# generator4.net
KiCad netlist of a schematic drawn in EAGLE
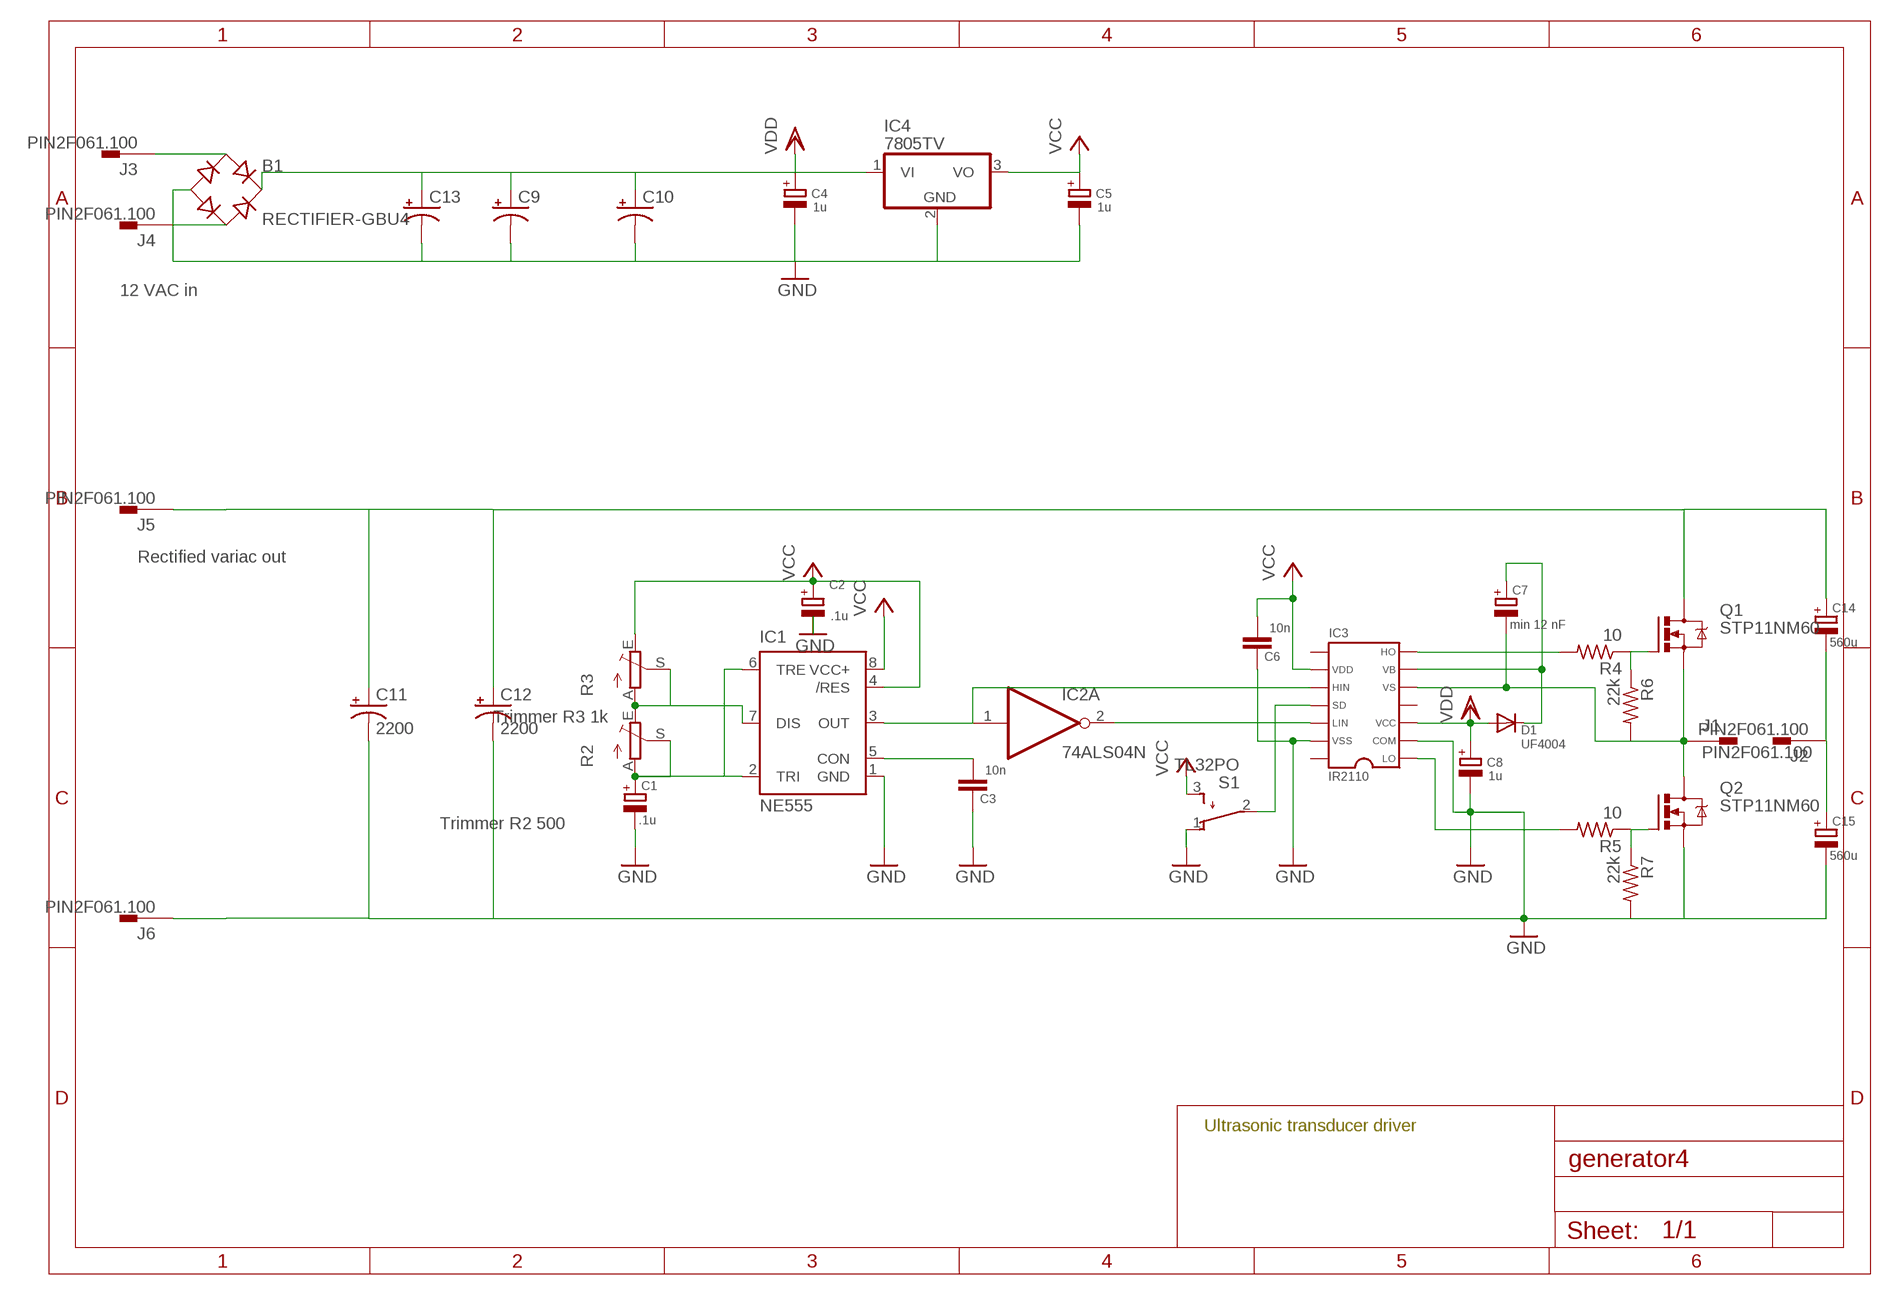
[diagram p0: schematic, sheet 1]

(export (version "E")
  (design (tool "Eeschema 10.0.6"))
  (components
    (comp (ref "B1")
      (value "RECTIFIER-GBU4")
      (footprint "eagle-import:GBU4")
      (libsource (lib "eagle-import") (part "RECTIFIER-GBU4"))
    )
    (comp (ref "C1")
      (value ".1u")
      (footprint "eagle-import:E5-8,5")
      (libsource (lib "eagle-import") (part "CPOL-EUE5-8.5"))
    )
    (comp (ref "C2")
      (value ".1u")
      (footprint "eagle-import:E5-8,5")
      (libsource (lib "eagle-import") (part "CPOL-EUE5-8.5"))
    )
    (comp (ref "C3")
      (value "10n")
      (footprint "eagle-import:C075-052X106")
      (libsource (lib "eagle-import") (part "C-EU075-052X106"))
    )
    (comp (ref "C4")
      (value "1u")
      (footprint "eagle-import:E5-8,5")
      (libsource (lib "eagle-import") (part "CPOL-EUE5-8.5"))
    )
    (comp (ref "C5")
      (value "1u")
      (footprint "eagle-import:E5-8,5")
      (libsource (lib "eagle-import") (part "CPOL-EUE5-8.5"))
    )
    (comp (ref "C6")
      (value "10n")
      (footprint "eagle-import:C075-052X106")
      (libsource (lib "eagle-import") (part "C-EU075-052X106"))
    )
    (comp (ref "C7")
      (value "min 12 nF")
      (footprint "eagle-import:E5-8,5")
      (libsource (lib "eagle-import") (part "CPOL-EUE5-8.5"))
    )
    (comp (ref "C8")
      (value "1u")
      (footprint "eagle-import:E5-8,5")
      (libsource (lib "eagle-import") (part "CPOL-EUE5-8.5"))
    )
    (comp (ref "C9")
      (value "CPOL-USE7.5-18")
      (footprint "eagle-import:E7,5-18")
      (libsource (lib "eagle-import") (part "CPOL-USE7.5-18"))
    )
    (comp (ref "C10")
      (value "CPOL-USE7.5-18")
      (footprint "eagle-import:E7,5-18")
      (libsource (lib "eagle-import") (part "CPOL-USE7.5-18"))
    )
    (comp (ref "C11")
      (value "2200")
      (footprint "eagle-import:EB35D")
      (libsource (lib "eagle-import") (part "CPOL-USE10-35"))
    )
    (comp (ref "C12")
      (value "2200")
      (footprint "eagle-import:EB35D")
      (libsource (lib "eagle-import") (part "CPOL-USE10-35"))
    )
    (comp (ref "C13")
      (value "CPOL-USE7.5-18")
      (footprint "eagle-import:E7,5-18")
      (libsource (lib "eagle-import") (part "CPOL-USE7.5-18"))
    )
    (comp (ref "C14")
      (value "560u")
      (footprint "eagle-import:E7,5-16")
      (libsource (lib "eagle-import") (part "CPOL-EUE7.5-16"))
    )
    (comp (ref "C15")
      (value "560u")
      (footprint "eagle-import:E7,5-16")
      (libsource (lib "eagle-import") (part "CPOL-EUE7.5-16"))
    )
    (comp (ref "D1")
      (value "UF4004")
      (footprint "eagle-import:D-7.5")
      (libsource (lib "eagle-import") (part "DIODE-D-7.5"))
    )
    (comp (ref "IC1")
      (value "NE555")
      (footprint "eagle-import:DIL-08")
      (fields (field (name "MF") "Arrow Electronics") (field (name "MPN") "NE555N"))
      (libsource (lib "eagle-import") (part "NE555"))
    )
    (comp (ref "IC2")
      (value "74ALS04N")
      (footprint "eagle-import:DIL14")
      (libsource (lib "eagle-import") (part "7404NALS"))
    )
    (comp (ref "IC3")
      (value "IR2110")
      (footprint "eagle-import:DIL14")
      (libsource (lib "eagle-import") (part "IR2110"))
    )
    (comp (ref "IC4")
      (value "7805TV")
      (footprint "eagle-import:TO220V")
      (libsource (lib "eagle-import") (part "78TV05"))
    )
    (comp (ref "J1")
      (value "PIN2F061.100")
      (footprint "eagle-import:F061.100")
      (libsource (lib "eagle-import") (part "PIN2F061.100"))
    )
    (comp (ref "J2")
      (value "PIN2F061.100")
      (footprint "eagle-import:F061.100")
      (libsource (lib "eagle-import") (part "PIN2F061.100"))
    )
    (comp (ref "J3")
      (value "PIN2F061.100")
      (footprint "eagle-import:F061.100")
      (libsource (lib "eagle-import") (part "PIN2F061.100"))
    )
    (comp (ref "J4")
      (value "PIN2F061.100")
      (footprint "eagle-import:F061.100")
      (libsource (lib "eagle-import") (part "PIN2F061.100"))
    )
    (comp (ref "J5")
      (value "PIN2F061.100")
      (footprint "eagle-import:F061.100")
      (libsource (lib "eagle-import") (part "PIN2F061.100"))
    )
    (comp (ref "J6")
      (value "PIN2F061.100")
      (footprint "eagle-import:F061.100")
      (libsource (lib "eagle-import") (part "PIN2F061.100"))
    )
    (comp (ref "Q1")
      (value "STP11NM60")
      (footprint "eagle-import:TO220BV")
      (libsource (lib "eagle-import") (part "IRF530"))
    )
    (comp (ref "Q2")
      (value "STP11NM60")
      (footprint "eagle-import:TO220BV")
      (libsource (lib "eagle-import") (part "IRF530"))
    )
    (comp (ref "R2")
      (value "TRIM_EU-LI10")
      (footprint "eagle-import:LI10")
      (libsource (lib "eagle-import") (part "TRIM_EU-LI10"))
    )
    (comp (ref "R3")
      (value "TRIM_EU-LI10")
      (footprint "eagle-import:LI10")
      (libsource (lib "eagle-import") (part "TRIM_EU-LI10"))
    )
    (comp (ref "R4")
      (value "10")
      (footprint "eagle-import:0207_10")
      (libsource (lib "eagle-import") (part "R-US_0207/10"))
    )
    (comp (ref "R5")
      (value "10")
      (footprint "eagle-import:0207_10")
      (libsource (lib "eagle-import") (part "R-US_0207/10"))
    )
    (comp (ref "R6")
      (value "22k")
      (footprint "eagle-import:0207_10")
      (libsource (lib "eagle-import") (part "R-US_0207/10"))
    )
    (comp (ref "R7")
      (value "22k")
      (footprint "eagle-import:0207_10")
      (libsource (lib "eagle-import") (part "R-US_0207/10"))
    )
    (comp (ref "S1")
      (value "TL32PO")
      (footprint "eagle-import:TL3XPO")
      (libsource (lib "eagle-import") (part "TL32PO"))
    )
  )
  (nets
    (net (code "1") (name "GND") (class "Default")
      (node (ref "B1") (pin "-") (pinfunction "-_-") (pintype "passive"))
      (node (ref "C1") (pin "-") (pinfunction "-_-") (pintype "passive"))
      (node (ref "C10") (pin "-") (pinfunction "-_-") (pintype "passive"))
      (node (ref "C11") (pin "-") (pinfunction "-_-") (pintype "passive"))
      (node (ref "C12") (pin "-") (pinfunction "-_-") (pintype "passive"))
      (node (ref "C13") (pin "-") (pinfunction "-_-") (pintype "passive"))
      (node (ref "C15") (pin "-") (pinfunction "-_-") (pintype "passive"))
      (node (ref "C2") (pin "-") (pinfunction "-_-") (pintype "passive"))
      (node (ref "C3") (pin "1") (pinfunction "1_1") (pintype "passive"))
      (node (ref "C4") (pin "-") (pinfunction "-_-") (pintype "passive"))
      (node (ref "C5") (pin "-") (pinfunction "-_-") (pintype "passive"))
      (node (ref "C6") (pin "1") (pinfunction "1_1") (pintype "passive"))
      (node (ref "C8") (pin "-") (pinfunction "-_-") (pintype "passive"))
      (node (ref "C9") (pin "-") (pinfunction "-_-") (pintype "passive"))
      (node (ref "IC1") (pin "1") (pinfunction "GND_1") (pintype "power_in"))
      (node (ref "IC3") (pin "13") (pinfunction "13_13") (pintype "passive"))
      (node (ref "IC3") (pin "2") (pinfunction "2_2") (pintype "passive"))
      (node (ref "IC4") (pin "2") (pinfunction "GND_2") (pintype "passive"))
      (node (ref "J6") (pin "A1") (pinfunction "1_A1") (pintype "passive"))
      (node (ref "J6") (pin "A2") (pinfunction "1_A2") (pintype "passive"))
      (node (ref "Q2") (pin "S") (pinfunction "S_S") (pintype "passive"))
      (node (ref "R7") (pin "2") (pinfunction "2_2") (pintype "passive"))
      (node (ref "S1") (pin "1") (pinfunction "O_1") (pintype "passive"))
    )
    (net (code "2") (name "Net-(B1-PadAC1)") (class "Default")
      (node (ref "B1") (pin "AC1") (pinfunction "AC1_AC1") (pintype "passive"))
      (node (ref "J3") (pin "A1") (pinfunction "1_A1") (pintype "passive"))
      (node (ref "J3") (pin "A2") (pinfunction "1_A2") (pintype "passive"))
    )
    (net (code "3") (name "Net-(B1-PadAC2)") (class "Default")
      (node (ref "B1") (pin "AC2") (pinfunction "AC2_AC2") (pintype "passive"))
      (node (ref "J4") (pin "A1") (pinfunction "1_A1") (pintype "passive"))
      (node (ref "J4") (pin "A2") (pinfunction "1_A2") (pintype "passive"))
    )
    (net (code "4") (name "Net-(C7-Pad+)") (class "Default")
      (node (ref "C7") (pin "+") (pinfunction "+_+") (pintype "passive"))
      (node (ref "D1") (pin "C") (pinfunction "C_C") (pintype "passive"))
      (node (ref "IC3") (pin "6") (pinfunction "6_6") (pintype "passive"))
    )
    (net (code "5") (name "Net-(C7-Pad-)") (class "Default")
      (node (ref "C7") (pin "-") (pinfunction "-_-") (pintype "passive"))
      (node (ref "IC3") (pin "5") (pinfunction "5_5") (pintype "passive"))
      (node (ref "J1") (pin "A1") (pinfunction "1_A1") (pintype "passive"))
      (node (ref "J1") (pin "A2") (pinfunction "1_A2") (pintype "passive"))
      (node (ref "Q1") (pin "S") (pinfunction "S_S") (pintype "passive"))
      (node (ref "Q2") (pin "D") (pinfunction "D_D") (pintype "passive"))
      (node (ref "R6") (pin "2") (pinfunction "2_2") (pintype "passive"))
    )
    (net (code "6") (name "Net-(C11-Pad+)") (class "Default")
      (node (ref "C11") (pin "+") (pinfunction "+_+") (pintype "passive"))
      (node (ref "C12") (pin "+") (pinfunction "+_+") (pintype "passive"))
      (node (ref "C14") (pin "+") (pinfunction "+_+") (pintype "passive"))
      (node (ref "J5") (pin "A1") (pinfunction "1_A1") (pintype "passive"))
      (node (ref "J5") (pin "A2") (pinfunction "1_A2") (pintype "passive"))
      (node (ref "Q1") (pin "D") (pinfunction "D_D") (pintype "passive"))
    )
    (net (code "7") (name "Net-(C14-Pad-)") (class "Default")
      (node (ref "C14") (pin "-") (pinfunction "-_-") (pintype "passive"))
      (node (ref "C15") (pin "+") (pinfunction "+_+") (pintype "passive"))
      (node (ref "J2") (pin "A1") (pinfunction "1_A1") (pintype "passive"))
      (node (ref "J2") (pin "A2") (pinfunction "1_A2") (pintype "passive"))
    )
    (net (code "8") (name "Net-(IC1-CON)") (class "Default")
      (node (ref "C3") (pin "2") (pinfunction "2_2") (pintype "passive"))
      (node (ref "IC1") (pin "5") (pinfunction "CON_5") (pintype "input"))
    )
    (net (code "9") (name "Net-(IC1-DIS)") (class "Default")
      (node (ref "IC1") (pin "7") (pinfunction "DIS_7") (pintype "input"))
      (node (ref "R2") (pin "E") (pinfunction "E_E") (pintype "passive"))
      (node (ref "R3") (pin "A") (pinfunction "A_A") (pintype "passive"))
      (node (ref "R3") (pin "S") (pinfunction "S_S") (pintype "passive"))
    )
    (net (code "10") (name "Net-(IC1-OUT)") (class "Default")
      (node (ref "IC1") (pin "3") (pinfunction "OUT_3") (pintype "output"))
      (node (ref "IC2") (pin "1") (pinfunction "I_1") (pintype "input"))
      (node (ref "IC3") (pin "10") (pinfunction "10_10") (pintype "passive"))
    )
    (net (code "11") (name "Net-(IC1-TRE)") (class "Default")
      (node (ref "C1") (pin "+") (pinfunction "+_+") (pintype "passive"))
      (node (ref "IC1") (pin "2") (pinfunction "TRI_2") (pintype "input"))
      (node (ref "IC1") (pin "6") (pinfunction "TRE_6") (pintype "input"))
      (node (ref "R2") (pin "A") (pinfunction "A_A") (pintype "passive"))
      (node (ref "R2") (pin "S") (pinfunction "S_S") (pintype "passive"))
    )
    (net (code "12") (name "Net-(IC2A-O)") (class "Default")
      (node (ref "IC2") (pin "2") (pinfunction "O_2") (pintype "output"))
      (node (ref "IC3") (pin "12") (pinfunction "12_12") (pintype "passive"))
    )
    (net (code "13") (name "Net-(IC3-Pad1)") (class "Default")
      (node (ref "IC3") (pin "1") (pinfunction "1_1") (pintype "passive"))
      (node (ref "R5") (pin "2") (pinfunction "2_2") (pintype "passive"))
    )
    (net (code "14") (name "Net-(IC3-Pad7)") (class "Default")
      (node (ref "IC3") (pin "7") (pinfunction "7_7") (pintype "passive"))
      (node (ref "R4") (pin "2") (pinfunction "2_2") (pintype "passive"))
    )
    (net (code "15") (name "Net-(Q1-PadG)") (class "Default")
      (node (ref "Q1") (pin "G") (pinfunction "G_G") (pintype "passive"))
      (node (ref "R4") (pin "1") (pinfunction "1_1") (pintype "passive"))
      (node (ref "R6") (pin "1") (pinfunction "1_1") (pintype "passive"))
    )
    (net (code "16") (name "Net-(Q2-PadG)") (class "Default")
      (node (ref "Q2") (pin "G") (pinfunction "G_G") (pintype "passive"))
      (node (ref "R5") (pin "1") (pinfunction "1_1") (pintype "passive"))
      (node (ref "R7") (pin "1") (pinfunction "1_1") (pintype "passive"))
    )
    (net (code "17") (name "Net-(S1-P)") (class "Default")
      (node (ref "IC3") (pin "11") (pinfunction "11_11") (pintype "passive"))
      (node (ref "S1") (pin "2") (pinfunction "P_2") (pintype "passive"))
    )
    (net (code "18") (name "VCC") (class "Default")
      (node (ref "C2") (pin "+") (pinfunction "+_+") (pintype "passive"))
      (node (ref "C5") (pin "+") (pinfunction "+_+") (pintype "passive"))
      (node (ref "C6") (pin "2") (pinfunction "2_2") (pintype "passive"))
      (node (ref "IC1") (pin "4") (pinfunction "/RES_4") (pintype "input"))
      (node (ref "IC1") (pin "8") (pinfunction "VCC+_8") (pintype "power_in"))
      (node (ref "IC3") (pin "9") (pinfunction "9_9") (pintype "passive"))
      (node (ref "IC4") (pin "3") (pinfunction "VO_3") (pintype "passive"))
      (node (ref "R3") (pin "E") (pinfunction "E_E") (pintype "passive"))
      (node (ref "S1") (pin "3") (pinfunction "S_3") (pintype "passive"))
    )
    (net (code "19") (name "VDD") (class "Default")
      (node (ref "B1") (pin "+") (pinfunction "+_+") (pintype "passive"))
      (node (ref "C10") (pin "+") (pinfunction "+_+") (pintype "passive"))
      (node (ref "C13") (pin "+") (pinfunction "+_+") (pintype "passive"))
      (node (ref "C4") (pin "+") (pinfunction "+_+") (pintype "passive"))
      (node (ref "C8") (pin "+") (pinfunction "+_+") (pintype "passive"))
      (node (ref "C9") (pin "+") (pinfunction "+_+") (pintype "passive"))
      (node (ref "D1") (pin "A") (pinfunction "A_A") (pintype "passive"))
      (node (ref "IC3") (pin "3") (pinfunction "3_3") (pintype "passive"))
      (node (ref "IC4") (pin "1") (pinfunction "VI_1") (pintype "input"))
    )
    (net (code "20") (name "unconnected-(IC3-Pad4)") (class "Default")
      (node (ref "IC3") (pin "4") (pinfunction "4_4") (pintype "passive"))
    )
    (net (code "21") (name "unconnected-(IC3-Pad8)") (class "Default")
      (node (ref "IC3") (pin "8") (pinfunction "8_8") (pintype "passive"))
    )
    (net (code "22") (name "unconnected-(IC3-Pad14)") (class "Default")
      (node (ref "IC3") (pin "14") (pinfunction "14_14") (pintype "passive"))
    )
  )
)
